# Prototipo_1_0.net
KiCad netlist of a schematic drawn in EAGLE
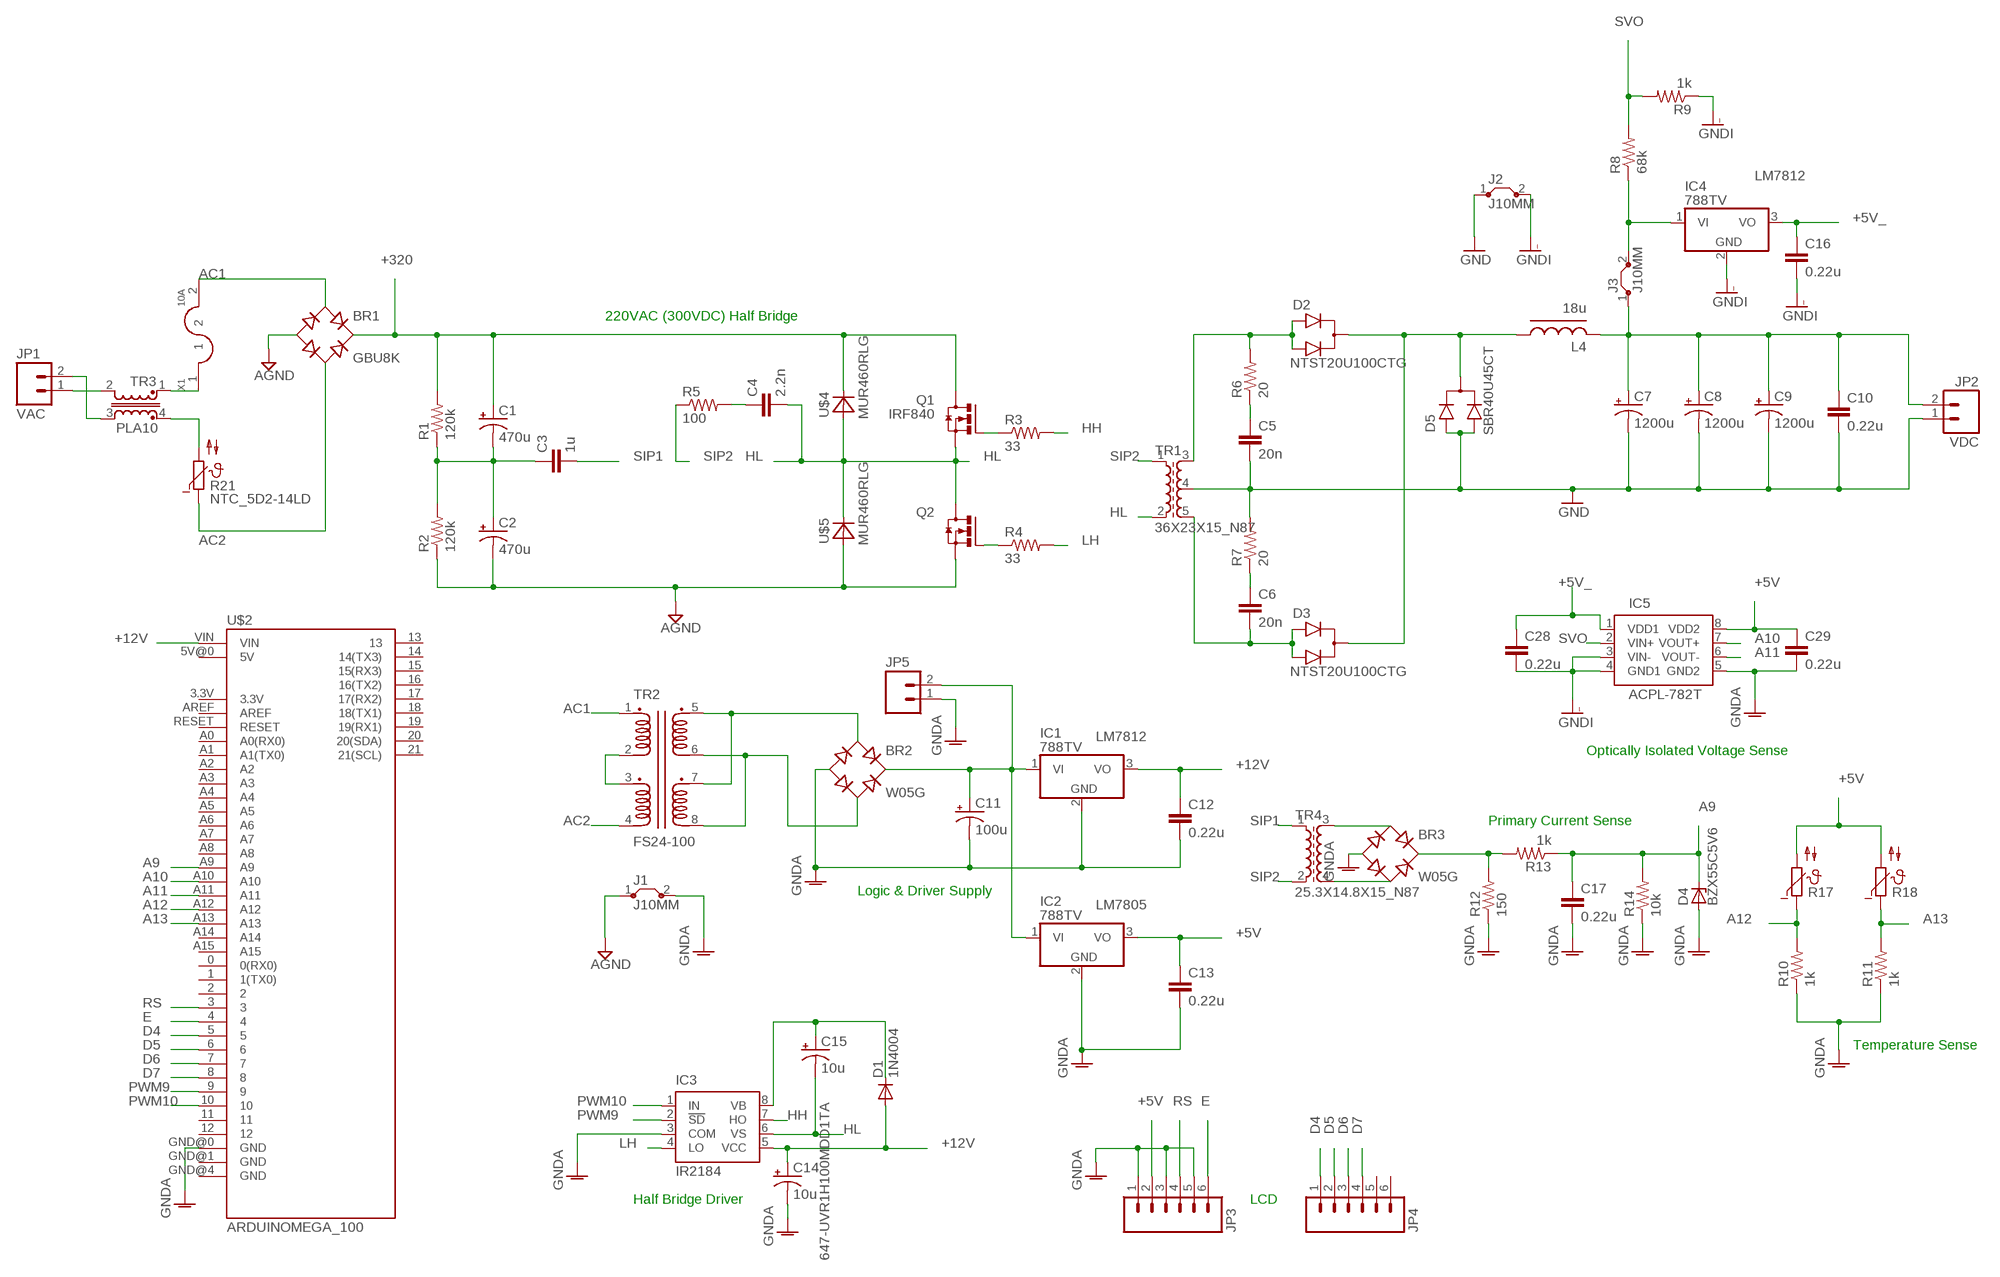
[diagram p0: schematic, sheet 1]

(export (version "E")
  (design (tool "Eeschema 10.0.6"))
  (components
    (comp (ref "BR1")
      (value "GBU8K")
      (footprint "eagle-import:GBU")
      (libsource (lib "eagle-import") (part "GBU8K"))
    )
    (comp (ref "BR2")
      (value "W05G")
      (footprint "eagle-import:WOG")
      (libsource (lib "eagle-import") (part "WG05"))
    )
    (comp (ref "BR3")
      (value "W05G")
      (footprint "eagle-import:WOG")
      (libsource (lib "eagle-import") (part "WG05"))
    )
    (comp (ref "C1")
      (value "470u")
      (footprint "eagle-import:CPOL_RADIAL_470UF_250V")
      (libsource (lib "eagle-import") (part "CAP_470UF_250V"))
    )
    (comp (ref "C2")
      (value "470u")
      (footprint "eagle-import:CPOL_RADIAL_470UF_250V")
      (libsource (lib "eagle-import") (part "CAP_470UF_250V"))
    )
    (comp (ref "C3")
      (value "1u")
      (footprint "eagle-import:C22.5B8")
      (libsource (lib "eagle-import") (part "C22/8"))
    )
    (comp (ref "C4")
      (value "2.2n")
      (footprint "eagle-import:C7.5B4")
      (libsource (lib "eagle-import") (part "C7.5/4"))
    )
    (comp (ref "C5")
      (value "20n")
      (footprint "eagle-import:C10B4")
      (libsource (lib "eagle-import") (part "C10/4"))
    )
    (comp (ref "C6")
      (value "20n")
      (footprint "eagle-import:C10B4")
      (libsource (lib "eagle-import") (part "C10/4"))
    )
    (comp (ref "C7")
      (value "1200u")
      (footprint "eagle-import:CPOL-RADIAL-1000UF-25V")
      (libsource (lib "eagle-import") (part "CAP_POLPTH4"))
    )
    (comp (ref "C8")
      (value "1200u")
      (footprint "eagle-import:CPOL-RADIAL-1000UF-25V")
      (libsource (lib "eagle-import") (part "CAP_POLPTH4"))
    )
    (comp (ref "C9")
      (value "1200u")
      (footprint "eagle-import:CPOL-RADIAL-1000UF-25V")
      (libsource (lib "eagle-import") (part "CAP_POLPTH4"))
    )
    (comp (ref "C10")
      (value "0.22u")
      (footprint "eagle-import:C5B3")
      (libsource (lib "eagle-import") (part "C5/3"))
    )
    (comp (ref "C11")
      (value "100u")
      (footprint "eagle-import:E3,5-8")
      (libsource (lib "eagle-import") (part "CPOL-USE3.5-8"))
    )
    (comp (ref "C12")
      (value "0.22u")
      (footprint "eagle-import:C5B3")
      (libsource (lib "eagle-import") (part "C5/3"))
    )
    (comp (ref "C13")
      (value "0.22u")
      (footprint "eagle-import:C5B3")
      (libsource (lib "eagle-import") (part "C5/3"))
    )
    (comp (ref "C14")
      (value "10u")
      (footprint "eagle-import:E2,5-6E")
      (fields (field (name "MOUSER") "647-UVR1H100MDD1TA"))
      (libsource (lib "eagle-import") (part "CPOL-USE2,5-6E"))
    )
    (comp (ref "C15")
      (value "10u")
      (footprint "eagle-import:E2,5-6E")
      (libsource (lib "eagle-import") (part "CPOL-USE2,5-6E"))
    )
    (comp (ref "C16")
      (value "0.22u")
      (footprint "eagle-import:C5B3")
      (libsource (lib "eagle-import") (part "C5/3"))
    )
    (comp (ref "C17")
      (value "0.22u")
      (footprint "eagle-import:C5B3")
      (libsource (lib "eagle-import") (part "C5/3"))
    )
    (comp (ref "C28")
      (value "0.22u")
      (footprint "eagle-import:C5B3")
      (libsource (lib "eagle-import") (part "C5/3"))
    )
    (comp (ref "C29")
      (value "0.22u")
      (footprint "eagle-import:C5B3")
      (libsource (lib "eagle-import") (part "C5/3"))
    )
    (comp (ref "D1")
      (value "1N4004")
      (footprint "eagle-import:DO41-10")
      (libsource (lib "eagle-import") (part "1N4004"))
    )
    (comp (ref "D2")
      (value "NTST20U100CTG")
      (footprint "eagle-import:TO220V")
      (libsource (lib "eagle-import") (part "NTST20U100CTG"))
    )
    (comp (ref "D3")
      (value "NTST20U100CTG")
      (footprint "eagle-import:TO220V")
      (libsource (lib "eagle-import") (part "NTST20U100CTG"))
    )
    (comp (ref "D4")
      (value "BZX55C5V6")
      (footprint "eagle-import:DO35Z10")
      (libsource (lib "eagle-import") (part "BZX55"))
    )
    (comp (ref "D5")
      (value "SBR40U45CT")
      (footprint "eagle-import:TO220V")
      (libsource (lib "eagle-import") (part "SBR40U45CT"))
    )
    (comp (ref "IC1")
      (value "788TV")
      (footprint "eagle-import:TO220V")
      (fields (field (name "MODEL") "LM7812"))
      (libsource (lib "eagle-import") (part "78TV8"))
    )
    (comp (ref "IC2")
      (value "788TV")
      (footprint "eagle-import:TO220V")
      (fields (field (name "MODEL") "LM7805"))
      (libsource (lib "eagle-import") (part "78TV8"))
    )
    (comp (ref "IC3")
      (value "IR2184")
      (footprint "eagle-import:DIL08")
      (fields (field (name "MF") "INTERNATIONAL RECTIFIER(IR)"))
      (libsource (lib "eagle-import") (part "IR2184"))
    )
    (comp (ref "IC4")
      (value "788TV")
      (footprint "eagle-import:TO220V")
      (fields (field (name "MODEL") "LM7812"))
      (libsource (lib "eagle-import") (part "78TV8"))
    )
    (comp (ref "IC5")
      (value "ACPL-782T")
      (footprint "eagle-import:DIL08")
      (libsource (lib "eagle-import") (part "ACPL-782T"))
    )
    (comp (ref "J1")
      (value "J10MM")
      (footprint "eagle-import:10")
      (libsource (lib "eagle-import") (part "J10MM"))
    )
    (comp (ref "J2")
      (value "J10MM")
      (footprint "eagle-import:10")
      (libsource (lib "eagle-import") (part "J10MM"))
    )
    (comp (ref "J3")
      (value "J10MM")
      (footprint "eagle-import:10")
      (libsource (lib "eagle-import") (part "J10MM"))
    )
    (comp (ref "JP1")
      (value "VAC")
      (footprint "eagle-import:SCREWTERMINAL-3.5MM-2")
      (libsource (lib "eagle-import") (part "M023.5MM"))
    )
    (comp (ref "JP2")
      (value "VDC")
      (footprint "eagle-import:SCREWTERMINAL-5MM-2")
      (libsource (lib "eagle-import") (part "M025MM"))
    )
    (comp (ref "JP3")
      (value "M06SIP")
      (footprint "eagle-import:1X06")
      (libsource (lib "eagle-import") (part "M06SIP"))
    )
    (comp (ref "JP4")
      (value "M06SIP")
      (footprint "eagle-import:1X06")
      (libsource (lib "eagle-import") (part "M06SIP"))
    )
    (comp (ref "JP5")
      (value "M02LOCK_LONGPADS")
      (footprint "eagle-import:1X02_LOCK_LONGPADS")
      (libsource (lib "eagle-import") (part "M02LOCK_LONGPADS"))
    )
    (comp (ref "L4")
      (value "18u")
      (footprint "eagle-import:CHOKE_18U")
      (libsource (lib "eagle-import") (part "CHOKE_18U"))
    )
    (comp (ref "Q1")
      (value "IRF840")
      (footprint "eagle-import:TO220HV")
      (libsource (lib "eagle-import") (part "IRF840"))
    )
    (comp (ref "Q2")
      (value "IRF840")
      (footprint "eagle-import:TO220HV")
      (libsource (lib "eagle-import") (part "IRF840"))
    )
    (comp (ref "R1")
      (value "120k")
      (footprint "eagle-import:AXIAL-0.4")
      (libsource (lib "eagle-import") (part "RESISTORPTH-1/4W"))
    )
    (comp (ref "R2")
      (value "120k")
      (footprint "eagle-import:AXIAL-0.4")
      (libsource (lib "eagle-import") (part "RESISTORPTH-1/4W"))
    )
    (comp (ref "R3")
      (value "33")
      (footprint "eagle-import:AXIAL-0.5")
      (libsource (lib "eagle-import") (part "RESISTORPTH-1/2W"))
    )
    (comp (ref "R4")
      (value "33")
      (footprint "eagle-import:AXIAL-0.5")
      (libsource (lib "eagle-import") (part "RESISTORPTH-1/2W"))
    )
    (comp (ref "R5")
      (value "100")
      (footprint "eagle-import:0922V")
      (libsource (lib "eagle-import") (part "R-US_0922V"))
    )
    (comp (ref "R6")
      (value "20")
      (footprint "eagle-import:AXIAL-0.5")
      (libsource (lib "eagle-import") (part "RESISTORPTH-1/2W"))
    )
    (comp (ref "R7")
      (value "20")
      (footprint "eagle-import:AXIAL-0.5")
      (libsource (lib "eagle-import") (part "RESISTORPTH-1/2W"))
    )
    (comp (ref "R8")
      (value "68k")
      (footprint "eagle-import:AXIAL-0.4")
      (libsource (lib "eagle-import") (part "RESISTORPTH-1/4W"))
    )
    (comp (ref "R9")
      (value "1k")
      (footprint "eagle-import:AXIAL-0.4")
      (libsource (lib "eagle-import") (part "RESISTORPTH-1/4W"))
    )
    (comp (ref "R10")
      (value "1k")
      (footprint "eagle-import:AXIAL-0.4")
      (libsource (lib "eagle-import") (part "RESISTORPTH-1/4W"))
    )
    (comp (ref "R11")
      (value "1k")
      (footprint "eagle-import:AXIAL-0.4")
      (libsource (lib "eagle-import") (part "RESISTORPTH-1/4W"))
    )
    (comp (ref "R12")
      (value "150")
      (footprint "eagle-import:AXIAL-0.4")
      (libsource (lib "eagle-import") (part "RESISTORPTH-1/4W"))
    )
    (comp (ref "R13")
      (value "1k")
      (footprint "eagle-import:AXIAL-0.4")
      (libsource (lib "eagle-import") (part "RESISTORPTH-1/4W"))
    )
    (comp (ref "R14")
      (value "10k")
      (footprint "eagle-import:AXIAL-0.4")
      (libsource (lib "eagle-import") (part "RESISTORPTH-1/4W"))
    )
    (comp (ref "R17")
      (value "NTC640")
      (footprint "eagle-import:P640")
      (libsource (lib "eagle-import") (part "NTC640"))
    )
    (comp (ref "R18")
      (value "NTC640")
      (footprint "eagle-import:P640")
      (fields (field (name "OC_FARNELL") "unknown") (field (name "OC_NEWARK") "unknown"))
      (libsource (lib "eagle-import") (part "NTC640"))
    )
    (comp (ref "R21")
      (value "NTC_5D2-14LD")
      (footprint "eagle-import:C075-042X103")
      (libsource (lib "eagle-import") (part "NTC_5D2-14LD"))
    )
    (comp (ref "TR1")
      (value "36X23X15_N87")
      (footprint "eagle-import:CORE_36X23X15")
      (libsource (lib "eagle-import") (part "36X23X15_N87"))
    )
    (comp (ref "TR2")
      (value "FS24-100")
      (footprint "eagle-import:FS24-100")
      (libsource (lib "eagle-import") (part "FS24-100"))
    )
    (comp (ref "TR3")
      (value "PLA10")
      (footprint "eagle-import:COMMON_MODE_CHOKE_PLA10")
      (libsource (lib "eagle-import") (part "COMMON_MODE_CHOKE_PLA10"))
    )
    (comp (ref "TR4")
      (value "25.3X14.8X15_N87")
      (footprint "eagle-import:CORE_25.3X14.8X15")
      (libsource (lib "eagle-import") (part "25.3X14.8X15_N87"))
    )
    (comp (ref "U$2")
      (value "ARDUINOMEGA_100")
      (footprint "eagle-import:ARDUINOMEGA_100")
      (libsource (lib "eagle-import") (part "ARDUINOMEGA_100"))
    )
    (comp (ref "U$4")
      (value "MUR460RLG")
      (footprint "eagle-import:CB429-17")
      (libsource (lib "eagle-import") (part "MUR460RLG"))
    )
    (comp (ref "U$5")
      (value "MUR460RLG")
      (footprint "eagle-import:CB429-17")
      (libsource (lib "eagle-import") (part "MUR460RLG"))
    )
    (comp (ref "X1")
      (value "10A")
      (footprint "eagle-import:FUSE_HOLDER_5X20")
      (libsource (lib "eagle-import") (part "FUSE_HOLDER_5X20"))
    )
  )
  (nets
    (net (code "1") (name "/+5V") (class "Default")
      (node (ref "C13") (pin "1") (pinfunction "1_1") (pintype "passive"))
      (node (ref "C29") (pin "1") (pinfunction "1_1") (pintype "passive"))
      (node (ref "IC2") (pin "3") (pinfunction "VO_3") (pintype "passive"))
      (node (ref "IC5") (pin "8") (pinfunction "VDD2_8") (pintype "power_in"))
      (node (ref "JP3") (pin "2") (pinfunction "2_2") (pintype "passive"))
      (node (ref "R17") (pin "2") (pinfunction "2_2") (pintype "passive"))
      (node (ref "R18") (pin "2") (pinfunction "2_2") (pintype "passive"))
    )
    (net (code "2") (name "/+5V_") (class "Default")
      (node (ref "C16") (pin "1") (pinfunction "1_1") (pintype "passive"))
      (node (ref "C28") (pin "1") (pinfunction "1_1") (pintype "passive"))
      (node (ref "IC4") (pin "3") (pinfunction "VO_3") (pintype "passive"))
      (node (ref "IC5") (pin "1") (pinfunction "VDD1_1") (pintype "power_in"))
    )
    (net (code "3") (name "/+12V") (class "Default")
      (node (ref "C12") (pin "1") (pinfunction "1_1") (pintype "passive"))
      (node (ref "C14") (pin "+") (pinfunction "+_+") (pintype "passive"))
      (node (ref "D1") (pin "A") (pinfunction "A_A") (pintype "passive"))
      (node (ref "IC1") (pin "3") (pinfunction "VO_3") (pintype "passive"))
      (node (ref "IC3") (pin "5") (pinfunction "VCC_5") (pintype "output"))
      (node (ref "U$2") (pin "VIN") (pinfunction "VIN_VIN") (pintype "bidirectional"))
    )
    (net (code "4") (name "/+320") (class "Default")
      (node (ref "BR1") (pin "4") (pinfunction "+_4") (pintype "passive"))
      (node (ref "C1") (pin "1") (pinfunction "+_1") (pintype "passive"))
      (node (ref "Q1") (pin "2") (pinfunction "D_2") (pintype "passive"))
      (node (ref "R1") (pin "P$2") (pinfunction "2_P$2") (pintype "passive"))
      (node (ref "U$4") (pin "C") (pinfunction "C_C") (pintype "passive"))
    )
    (net (code "5") (name "/A9") (class "Default")
      (node (ref "C17") (pin "1") (pinfunction "1_1") (pintype "passive"))
      (node (ref "D4") (pin "C") (pinfunction "C_C") (pintype "passive"))
      (node (ref "R13") (pin "P$1") (pinfunction "1_P$1") (pintype "passive"))
      (node (ref "R14") (pin "P$2") (pinfunction "2_P$2") (pintype "passive"))
      (node (ref "U$2") (pin "A9") (pinfunction "A9_A9") (pintype "bidirectional"))
    )
    (net (code "6") (name "/A10") (class "Default")
      (node (ref "IC5") (pin "7") (pinfunction "VOUT+_7") (pintype "output"))
      (node (ref "U$2") (pin "A10") (pinfunction "A10_A10") (pintype "bidirectional"))
    )
    (net (code "7") (name "/A11") (class "Default")
      (node (ref "IC5") (pin "6") (pinfunction "VOUT-_6") (pintype "output"))
      (node (ref "U$2") (pin "A11") (pinfunction "A11_A11") (pintype "bidirectional"))
    )
    (net (code "8") (name "/A12") (class "Default")
      (node (ref "R10") (pin "P$2") (pinfunction "2_P$2") (pintype "passive"))
      (node (ref "R17") (pin "1") (pinfunction "1_1") (pintype "passive"))
      (node (ref "U$2") (pin "A12") (pinfunction "A12_A12") (pintype "bidirectional"))
    )
    (net (code "9") (name "/A13") (class "Default")
      (node (ref "R11") (pin "P$2") (pinfunction "2_P$2") (pintype "passive"))
      (node (ref "R18") (pin "1") (pinfunction "1_1") (pintype "passive"))
      (node (ref "U$2") (pin "A13") (pinfunction "A13_A13") (pintype "bidirectional"))
    )
    (net (code "10") (name "/AC1") (class "Default")
      (node (ref "BR1") (pin "2") (pinfunction "AC1_2") (pintype "passive"))
      (node (ref "TR2") (pin "1") (pinfunction "P1.1_1") (pintype "passive"))
      (node (ref "X1") (pin "2") (pinfunction "2_2") (pintype "bidirectional"))
    )
    (net (code "11") (name "/AC2") (class "Default")
      (node (ref "BR1") (pin "3") (pinfunction "AC2_3") (pintype "passive"))
      (node (ref "R21") (pin "1") (pinfunction "1_1") (pintype "passive"))
      (node (ref "TR2") (pin "4") (pinfunction "P2.2_4") (pintype "passive"))
    )
    (net (code "12") (name "/D4") (class "Default")
      (node (ref "JP4") (pin "1") (pinfunction "1_1") (pintype "passive"))
      (node (ref "U$2") (pin "5") (pinfunction "5_5") (pintype "bidirectional"))
    )
    (net (code "13") (name "/D5") (class "Default")
      (node (ref "JP4") (pin "2") (pinfunction "2_2") (pintype "passive"))
      (node (ref "U$2") (pin "6") (pinfunction "6_6") (pintype "bidirectional"))
    )
    (net (code "14") (name "/D6") (class "Default")
      (node (ref "JP4") (pin "3") (pinfunction "3_3") (pintype "passive"))
      (node (ref "U$2") (pin "7") (pinfunction "7_7") (pintype "bidirectional"))
    )
    (net (code "15") (name "/D7") (class "Default")
      (node (ref "JP4") (pin "4") (pinfunction "4_4") (pintype "passive"))
      (node (ref "U$2") (pin "8") (pinfunction "8_8") (pintype "bidirectional"))
    )
    (net (code "16") (name "/E") (class "Default")
      (node (ref "JP3") (pin "6") (pinfunction "6_6") (pintype "passive"))
      (node (ref "U$2") (pin "4") (pinfunction "4_4") (pintype "bidirectional"))
    )
    (net (code "17") (name "/HH") (class "Default")
      (node (ref "IC3") (pin "7") (pinfunction "HO_7") (pintype "passive"))
      (node (ref "R3") (pin "P$2") (pinfunction "2_P$2") (pintype "passive"))
    )
    (net (code "18") (name "/HL") (class "Default")
      (node (ref "C15") (pin "-") (pinfunction "-_-") (pintype "passive"))
      (node (ref "C4") (pin "2") (pinfunction "2_2") (pintype "passive"))
      (node (ref "IC3") (pin "6") (pinfunction "VS_6") (pintype "input"))
      (node (ref "Q1") (pin "3") (pinfunction "S_3") (pintype "passive"))
      (node (ref "Q2") (pin "2") (pinfunction "D_2") (pintype "passive"))
      (node (ref "TR1") (pin "2") (pinfunction "2_2") (pintype "passive"))
      (node (ref "U$4") (pin "A") (pinfunction "A_A") (pintype "passive"))
      (node (ref "U$5") (pin "C") (pinfunction "C_C") (pintype "passive"))
    )
    (net (code "19") (name "/LH") (class "Default")
      (node (ref "IC3") (pin "4") (pinfunction "LO_4") (pintype "power_in"))
      (node (ref "R4") (pin "P$2") (pinfunction "2_P$2") (pintype "passive"))
    )
    (net (code "20") (name "/PWM9") (class "Default")
      (node (ref "IC3") (pin "2") (pinfunction "~{SD}_2") (pintype "input"))
      (node (ref "U$2") (pin "9") (pinfunction "9_9") (pintype "bidirectional"))
    )
    (net (code "21") (name "/PWM10") (class "Default")
      (node (ref "IC3") (pin "1") (pinfunction "IN_1") (pintype "power_in"))
      (node (ref "U$2") (pin "10") (pinfunction "10_10") (pintype "bidirectional"))
    )
    (net (code "22") (name "/RS") (class "Default")
      (node (ref "JP3") (pin "4") (pinfunction "4_4") (pintype "passive"))
      (node (ref "U$2") (pin "3") (pinfunction "3_3") (pintype "bidirectional"))
    )
    (net (code "23") (name "/SIP1") (class "Default")
      (node (ref "C3") (pin "2") (pinfunction "2_2") (pintype "passive"))
      (node (ref "TR4") (pin "1") (pinfunction "1_1") (pintype "passive"))
    )
    (net (code "24") (name "/SIP2") (class "Default")
      (node (ref "R5") (pin "1") (pinfunction "1_1") (pintype "passive"))
      (node (ref "TR1") (pin "1") (pinfunction "1_1") (pintype "passive"))
      (node (ref "TR4") (pin "2") (pinfunction "2_2") (pintype "passive"))
    )
    (net (code "25") (name "/SVO") (class "Default")
      (node (ref "IC5") (pin "2") (pinfunction "VIN+_2") (pintype "input"))
      (node (ref "R8") (pin "P$2") (pinfunction "2_P$2") (pintype "passive"))
      (node (ref "R9") (pin "P$2") (pinfunction "2_P$2") (pintype "passive"))
    )
    (net (code "26") (name "AGND") (class "Default")
      (node (ref "BR1") (pin "1") (pinfunction "-_1") (pintype "passive"))
      (node (ref "C2") (pin "2") (pinfunction "-_2") (pintype "passive"))
      (node (ref "J1") (pin "1") (pinfunction "1_1") (pintype "passive"))
      (node (ref "Q2") (pin "3") (pinfunction "S_3") (pintype "passive"))
      (node (ref "R2") (pin "P$1") (pinfunction "1_P$1") (pintype "passive"))
      (node (ref "U$5") (pin "A") (pinfunction "A_A") (pintype "passive"))
    )
    (net (code "27") (name "GND") (class "Default")
      (node (ref "C10") (pin "2") (pinfunction "2_2") (pintype "passive"))
      (node (ref "C5") (pin "2") (pinfunction "2_2") (pintype "passive"))
      (node (ref "C7") (pin "2") (pinfunction "-_2") (pintype "passive"))
      (node (ref "C8") (pin "2") (pinfunction "-_2") (pintype "passive"))
      (node (ref "C9") (pin "2") (pinfunction "-_2") (pintype "passive"))
      (node (ref "D5") (pin "1") (pinfunction "A1_1") (pintype "passive"))
      (node (ref "D5") (pin "3") (pinfunction "A2_3") (pintype "passive"))
      (node (ref "J2") (pin "1") (pinfunction "1_1") (pintype "passive"))
      (node (ref "JP2") (pin "1") (pinfunction "1_1") (pintype "passive"))
      (node (ref "R7") (pin "P$2") (pinfunction "2_P$2") (pintype "passive"))
      (node (ref "TR1") (pin "4") (pinfunction "4_4") (pintype "passive"))
    )
    (net (code "28") (name "GNDA") (class "Default")
      (node (ref "BR2") (pin "-") (pinfunction "-_-") (pintype "passive"))
      (node (ref "BR3") (pin "-") (pinfunction "-_-") (pintype "passive"))
      (node (ref "C11") (pin "-") (pinfunction "-_-") (pintype "passive"))
      (node (ref "C12") (pin "2") (pinfunction "2_2") (pintype "passive"))
      (node (ref "C13") (pin "2") (pinfunction "2_2") (pintype "passive"))
      (node (ref "C14") (pin "-") (pinfunction "-_-") (pintype "passive"))
      (node (ref "C17") (pin "2") (pinfunction "2_2") (pintype "passive"))
      (node (ref "C29") (pin "2") (pinfunction "2_2") (pintype "passive"))
      (node (ref "D4") (pin "A") (pinfunction "A_A") (pintype "passive"))
      (node (ref "IC1") (pin "2") (pinfunction "GND_2") (pintype "passive"))
      (node (ref "IC2") (pin "2") (pinfunction "GND_2") (pintype "passive"))
      (node (ref "IC3") (pin "3") (pinfunction "COM_3") (pintype "input"))
      (node (ref "IC5") (pin "5") (pinfunction "GND2_5") (pintype "power_in"))
      (node (ref "J1") (pin "2") (pinfunction "2_2") (pintype "passive"))
      (node (ref "JP3") (pin "1") (pinfunction "1_1") (pintype "passive"))
      (node (ref "JP3") (pin "3") (pinfunction "3_3") (pintype "passive"))
      (node (ref "JP3") (pin "5") (pinfunction "5_5") (pintype "passive"))
      (node (ref "JP5") (pin "1") (pinfunction "1_1") (pintype "passive"))
      (node (ref "R10") (pin "P$1") (pinfunction "1_P$1") (pintype "passive"))
      (node (ref "R11") (pin "P$1") (pinfunction "1_P$1") (pintype "passive"))
      (node (ref "R12") (pin "P$1") (pinfunction "1_P$1") (pintype "passive"))
      (node (ref "R14") (pin "P$1") (pinfunction "1_P$1") (pintype "passive"))
      (node (ref "U$2") (pin "GND@0") (pinfunction "GND_GND@0") (pintype "bidirectional"))
    )
    (net (code "29") (name "GNDI") (class "Default")
      (node (ref "C16") (pin "2") (pinfunction "2_2") (pintype "passive"))
      (node (ref "C28") (pin "2") (pinfunction "2_2") (pintype "passive"))
      (node (ref "IC4") (pin "2") (pinfunction "GND_2") (pintype "passive"))
      (node (ref "IC5") (pin "3") (pinfunction "VIN-_3") (pintype "input"))
      (node (ref "IC5") (pin "4") (pinfunction "GND1_4") (pintype "power_in"))
      (node (ref "J2") (pin "2") (pinfunction "2_2") (pintype "passive"))
      (node (ref "R9") (pin "P$1") (pinfunction "1_P$1") (pintype "passive"))
    )
    (net (code "30") (name "Net-(BR3-PadAC1)") (class "Default")
      (node (ref "BR3") (pin "AC1") (pinfunction "AC1_AC1") (pintype "passive"))
      (node (ref "TR4") (pin "3") (pinfunction "3_3") (pintype "passive"))
    )
    (net (code "31") (name "Net-(BR3-PadAC2)") (class "Default")
      (node (ref "BR3") (pin "AC2") (pinfunction "AC2_AC2") (pintype "passive"))
      (node (ref "TR4") (pin "4") (pinfunction "4_4") (pintype "passive"))
    )
    (net (code "32") (name "Net-(C1--)") (class "Default")
      (node (ref "C1") (pin "2") (pinfunction "-_2") (pintype "passive"))
      (node (ref "C2") (pin "1") (pinfunction "+_1") (pintype "passive"))
      (node (ref "C3") (pin "1") (pinfunction "1_1") (pintype "passive"))
      (node (ref "R1") (pin "P$1") (pinfunction "1_P$1") (pintype "passive"))
      (node (ref "R2") (pin "P$2") (pinfunction "2_P$2") (pintype "passive"))
    )
    (net (code "33") (name "Net-(C4-Pad1)") (class "Default")
      (node (ref "C4") (pin "1") (pinfunction "1_1") (pintype "passive"))
      (node (ref "R5") (pin "2") (pinfunction "2_2") (pintype "passive"))
    )
    (net (code "34") (name "Net-(C7-+)") (class "Default")
      (node (ref "C10") (pin "1") (pinfunction "1_1") (pintype "passive"))
      (node (ref "C7") (pin "1") (pinfunction "+_1") (pintype "passive"))
      (node (ref "C8") (pin "1") (pinfunction "+_1") (pintype "passive"))
      (node (ref "C9") (pin "1") (pinfunction "+_1") (pintype "passive"))
      (node (ref "J3") (pin "1") (pinfunction "1_1") (pintype "passive"))
      (node (ref "JP2") (pin "2") (pinfunction "2_2") (pintype "passive"))
      (node (ref "L4") (pin "2") (pinfunction "2_2") (pintype "passive"))
    )
    (net (code "35") (name "Net-(D2-A1)") (class "Default")
      (node (ref "D2") (pin "1") (pinfunction "A1_1") (pintype "passive"))
      (node (ref "D2") (pin "3") (pinfunction "A2_3") (pintype "passive"))
      (node (ref "R6") (pin "P$2") (pinfunction "2_P$2") (pintype "passive"))
      (node (ref "TR1") (pin "3") (pinfunction "3_3") (pintype "passive"))
    )
    (net (code "36") (name "Net-(D2-C)") (class "Default")
      (node (ref "D2") (pin "2") (pinfunction "C_2") (pintype "passive"))
      (node (ref "D3") (pin "2") (pinfunction "C_2") (pintype "passive"))
      (node (ref "D5") (pin "2") (pinfunction "C_2") (pintype "passive"))
      (node (ref "L4") (pin "1") (pinfunction "1_1") (pintype "passive"))
    )
    (net (code "37") (name "Net-(D3-A1)") (class "Default")
      (node (ref "C6") (pin "2") (pinfunction "2_2") (pintype "passive"))
      (node (ref "D3") (pin "1") (pinfunction "A1_1") (pintype "passive"))
      (node (ref "D3") (pin "3") (pinfunction "A2_3") (pintype "passive"))
      (node (ref "TR1") (pin "5") (pinfunction "5_5") (pintype "passive"))
    )
    (net (code "38") (name "Net-(IC1-VI)") (class "Default")
      (node (ref "BR2") (pin "+") (pinfunction "+_+") (pintype "passive"))
      (node (ref "C11") (pin "+") (pinfunction "+_+") (pintype "passive"))
      (node (ref "IC1") (pin "1") (pinfunction "VI_1") (pintype "input"))
      (node (ref "IC2") (pin "1") (pinfunction "VI_1") (pintype "input"))
      (node (ref "JP5") (pin "2") (pinfunction "2_2") (pintype "passive"))
    )
    (net (code "39") (name "Net-(IC3-VB)") (class "Default")
      (node (ref "C15") (pin "+") (pinfunction "+_+") (pintype "passive"))
      (node (ref "D1") (pin "C") (pinfunction "C_C") (pintype "passive"))
      (node (ref "IC3") (pin "8") (pinfunction "VB_8") (pintype "output"))
    )
    (net (code "40") (name "Net-(IC4-VI)") (class "Default")
      (node (ref "IC4") (pin "1") (pinfunction "VI_1") (pintype "input"))
      (node (ref "J3") (pin "2") (pinfunction "2_2") (pintype "passive"))
      (node (ref "R8") (pin "P$1") (pinfunction "1_P$1") (pintype "passive"))
    )
    (net (code "41") (name "Net-(JP1-Pad1)") (class "Default")
      (node (ref "JP1") (pin "1") (pinfunction "1_1") (pintype "passive"))
      (node (ref "TR3") (pin "2") (pinfunction "2_2") (pintype "passive"))
    )
    (net (code "42") (name "Net-(JP1-Pad2)") (class "Default")
      (node (ref "JP1") (pin "2") (pinfunction "2_2") (pintype "passive"))
      (node (ref "TR3") (pin "3") (pinfunction "3_3") (pintype "passive"))
    )
    (net (code "43") (name "Net-(Q1-G)") (class "Default")
      (node (ref "Q1") (pin "1") (pinfunction "G_1") (pintype "passive"))
      (node (ref "R3") (pin "P$1") (pinfunction "1_P$1") (pintype "passive"))
    )
    (net (code "44") (name "Net-(Q2-G)") (class "Default")
      (node (ref "Q2") (pin "1") (pinfunction "G_1") (pintype "passive"))
      (node (ref "R4") (pin "P$1") (pinfunction "1_P$1") (pintype "passive"))
    )
    (net (code "45") (name "Net-(R6-1)") (class "Default")
      (node (ref "C5") (pin "1") (pinfunction "1_1") (pintype "passive"))
      (node (ref "R6") (pin "P$1") (pinfunction "1_P$1") (pintype "passive"))
    )
    (net (code "46") (name "Net-(R7-1)") (class "Default")
      (node (ref "C6") (pin "1") (pinfunction "1_1") (pintype "passive"))
      (node (ref "R7") (pin "P$1") (pinfunction "1_P$1") (pintype "passive"))
    )
    (net (code "47") (name "Net-(R12-2)") (class "Default")
      (node (ref "BR3") (pin "+") (pinfunction "+_+") (pintype "passive"))
      (node (ref "R12") (pin "P$2") (pinfunction "2_P$2") (pintype "passive"))
      (node (ref "R13") (pin "P$2") (pinfunction "2_P$2") (pintype "passive"))
    )
    (net (code "48") (name "Net-(R21-Pad2)") (class "Default")
      (node (ref "R21") (pin "2") (pinfunction "2_2") (pintype "passive"))
      (node (ref "TR3") (pin "4") (pinfunction "4_4") (pintype "passive"))
    )
    (net (code "49") (name "Net-(TR2-P1.2)") (class "Default")
      (node (ref "TR2") (pin "2") (pinfunction "P1.2_2") (pintype "passive"))
      (node (ref "TR2") (pin "3") (pinfunction "P2.1_3") (pintype "passive"))
    )
    (net (code "50") (name "Net-(TR2-S1.1)") (class "Default")
      (node (ref "BR2") (pin "AC1") (pinfunction "AC1_AC1") (pintype "passive"))
      (node (ref "TR2") (pin "5") (pinfunction "S1.1_5") (pintype "passive"))
      (node (ref "TR2") (pin "7") (pinfunction "S2.1_7") (pintype "passive"))
    )
    (net (code "51") (name "Net-(TR2-S1.2)") (class "Default")
      (node (ref "BR2") (pin "AC2") (pinfunction "AC2_AC2") (pintype "passive"))
      (node (ref "TR2") (pin "6") (pinfunction "S1.2_6") (pintype "passive"))
      (node (ref "TR2") (pin "8") (pinfunction "S2.2_8") (pintype "passive"))
    )
    (net (code "52") (name "Net-(TR3-Pad1)") (class "Default")
      (node (ref "TR3") (pin "1") (pinfunction "1_1") (pintype "passive"))
      (node (ref "X1") (pin "1") (pinfunction "1_1") (pintype "bidirectional"))
    )
    (net (code "53") (name "unconnected-(JP4-Pad5)") (class "Default")
      (node (ref "JP4") (pin "5") (pinfunction "5_5") (pintype "passive"))
    )
    (net (code "54") (name "unconnected-(JP4-Pad6)") (class "Default")
      (node (ref "JP4") (pin "6") (pinfunction "6_6") (pintype "passive"))
    )
    (net (code "55") (name "unconnected-(U$2-0(RX0)-Pad0)") (class "Default")
      (node (ref "U$2") (pin "0") (pinfunction "0(RX0)_0") (pintype "bidirectional"))
    )
    (net (code "56") (name "unconnected-(U$2-1(TX0)-Pad1)") (class "Default")
      (node (ref "U$2") (pin "1") (pinfunction "1(TX0)_1") (pintype "bidirectional"))
    )
    (net (code "57") (name "unconnected-(U$2-5V-Pad5V@0)") (class "Default")
      (node (ref "U$2") (pin "5V@0") (pinfunction "5V_5V@0") (pintype "bidirectional"))
    )
    (net (code "58") (name "unconnected-(U$2-14(TX3)-Pad14)") (class "Default")
      (node (ref "U$2") (pin "14") (pinfunction "14(TX3)_14") (pintype "bidirectional"))
    )
    (net (code "59") (name "unconnected-(U$2-15(RX3)-Pad15)") (class "Default")
      (node (ref "U$2") (pin "15") (pinfunction "15(RX3)_15") (pintype "bidirectional"))
    )
    (net (code "60") (name "unconnected-(U$2-16(TX2)-Pad16)") (class "Default")
      (node (ref "U$2") (pin "16") (pinfunction "16(TX2)_16") (pintype "bidirectional"))
    )
    (net (code "61") (name "unconnected-(U$2-17(RX2)-Pad17)") (class "Default")
      (node (ref "U$2") (pin "17") (pinfunction "17(RX2)_17") (pintype "bidirectional"))
    )
    (net (code "62") (name "unconnected-(U$2-18(TX1)-Pad18)") (class "Default")
      (node (ref "U$2") (pin "18") (pinfunction "18(TX1)_18") (pintype "bidirectional"))
    )
    (net (code "63") (name "unconnected-(U$2-19(RX1)-Pad19)") (class "Default")
      (node (ref "U$2") (pin "19") (pinfunction "19(RX1)_19") (pintype "bidirectional"))
    )
    (net (code "64") (name "unconnected-(U$2-20(SDA)-Pad20)") (class "Default")
      (node (ref "U$2") (pin "20") (pinfunction "20(SDA)_20") (pintype "bidirectional"))
    )
    (net (code "65") (name "unconnected-(U$2-21(SCL)-Pad21)") (class "Default")
      (node (ref "U$2") (pin "21") (pinfunction "21(SCL)_21") (pintype "bidirectional"))
    )
    (net (code "66") (name "unconnected-(U$2-A0(RX0)-PadA0)") (class "Default")
      (node (ref "U$2") (pin "A0") (pinfunction "A0(RX0)_A0") (pintype "bidirectional"))
    )
    (net (code "67") (name "unconnected-(U$2-A1(TX0)-PadA1)") (class "Default")
      (node (ref "U$2") (pin "A1") (pinfunction "A1(TX0)_A1") (pintype "bidirectional"))
    )
    (net (code "68") (name "unconnected-(U$2-GND-PadGND@1)") (class "Default")
      (node (ref "U$2") (pin "GND@1") (pinfunction "GND_GND@1") (pintype "bidirectional"))
    )
    (net (code "69") (name "unconnected-(U$2-GND-PadGND@4)") (class "Default")
      (node (ref "U$2") (pin "GND@4") (pinfunction "GND_GND@4") (pintype "bidirectional"))
    )
    (net (code "70") (name "unconnected-(U$2-Pad2)") (class "Default")
      (node (ref "U$2") (pin "2") (pinfunction "2_2") (pintype "bidirectional"))
    )
    (net (code "71") (name "unconnected-(U$2-Pad3.3V)") (class "Default")
      (node (ref "U$2") (pin "3.3V") (pinfunction "3.3V_3.3V") (pintype "bidirectional"))
    )
    (net (code "72") (name "unconnected-(U$2-Pad11)") (class "Default")
      (node (ref "U$2") (pin "11") (pinfunction "11_11") (pintype "bidirectional"))
    )
    (net (code "73") (name "unconnected-(U$2-Pad12)") (class "Default")
      (node (ref "U$2") (pin "12") (pinfunction "12_12") (pintype "bidirectional"))
    )
    (net (code "74") (name "unconnected-(U$2-Pad13)") (class "Default")
      (node (ref "U$2") (pin "13") (pinfunction "13_13") (pintype "bidirectional"))
    )
    (net (code "75") (name "unconnected-(U$2-PadA2)") (class "Default")
      (node (ref "U$2") (pin "A2") (pinfunction "A2_A2") (pintype "bidirectional"))
    )
    (net (code "76") (name "unconnected-(U$2-PadA3)") (class "Default")
      (node (ref "U$2") (pin "A3") (pinfunction "A3_A3") (pintype "bidirectional"))
    )
    (net (code "77") (name "unconnected-(U$2-PadA4)") (class "Default")
      (node (ref "U$2") (pin "A4") (pinfunction "A4_A4") (pintype "bidirectional"))
    )
    (net (code "78") (name "unconnected-(U$2-PadA5)") (class "Default")
      (node (ref "U$2") (pin "A5") (pinfunction "A5_A5") (pintype "bidirectional"))
    )
    (net (code "79") (name "unconnected-(U$2-PadA6)") (class "Default")
      (node (ref "U$2") (pin "A6") (pinfunction "A6_A6") (pintype "bidirectional"))
    )
    (net (code "80") (name "unconnected-(U$2-PadA7)") (class "Default")
      (node (ref "U$2") (pin "A7") (pinfunction "A7_A7") (pintype "bidirectional"))
    )
    (net (code "81") (name "unconnected-(U$2-PadA8)") (class "Default")
      (node (ref "U$2") (pin "A8") (pinfunction "A8_A8") (pintype "bidirectional"))
    )
    (net (code "82") (name "unconnected-(U$2-PadA14)") (class "Default")
      (node (ref "U$2") (pin "A14") (pinfunction "A14_A14") (pintype "bidirectional"))
    )
    (net (code "83") (name "unconnected-(U$2-PadA15)") (class "Default")
      (node (ref "U$2") (pin "A15") (pinfunction "A15_A15") (pintype "bidirectional"))
    )
    (net (code "84") (name "unconnected-(U$2-PadAREF)") (class "Default")
      (node (ref "U$2") (pin "AREF") (pinfunction "AREF_AREF") (pintype "bidirectional"))
    )
    (net (code "85") (name "unconnected-(U$2-PadRESET)") (class "Default")
      (node (ref "U$2") (pin "RESET") (pinfunction "RESET_RESET") (pintype "bidirectional"))
    )
  )
)
